# ST_SYS_Board_Clocking.net
KiCad netlist of a schematic drawn in Altium Designer
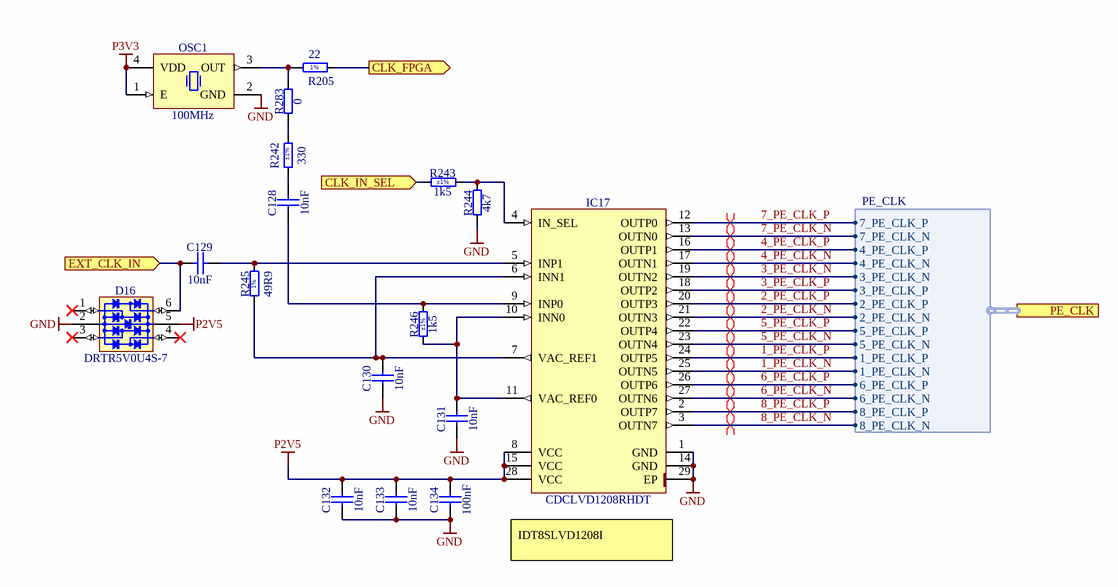
[diagram p0: ST_SYS_Board_Clocking.schdoc]

(export (version "E")
  (design (tool "Eeschema 10.0.6"))
  (components
    (comp (ref "C128")
      (value "10nF")
      (footprint "CAPC0603X33N")
      (description "Non-polarised capacitor")
      (fields
        (field (name "PART NUMBER") "CC0201_10NF_10V_10%_X5R")
        (field (name "VOLTAGE") "10V")
        (field (name "AUTHOR") "CERN DEM JLC")
      )
      (libsource (lib "Capacitors") (part "Capacitor - non polarized"))
    )
    (comp (ref "C129")
      (value "10nF")
      (footprint "CAPC0603X33N")
      (description "Non-polarised capacitor")
      (fields
        (field (name "PART NUMBER") "CC0201_10NF_10V_10%_X5R")
        (field (name "VOLTAGE") "10V")
        (field (name "AUTHOR") "CERN DEM JLC")
      )
      (libsource (lib "Capacitors") (part "Capacitor - non polarized"))
    )
    (comp (ref "C130")
      (value "10nF")
      (footprint "CAPC0603X33N")
      (description "Non-polarised capacitor")
      (fields
        (field (name "PART NUMBER") "CC0201_10NF_10V_10%_X5R")
        (field (name "VOLTAGE") "10V")
        (field (name "AUTHOR") "CERN DEM JLC")
      )
      (libsource (lib "Capacitors") (part "Capacitor - non polarized"))
    )
    (comp (ref "C131")
      (value "10nF")
      (footprint "CAPC0603X33N")
      (description "Non-polarised capacitor")
      (fields
        (field (name "PART NUMBER") "CC0201_10NF_10V_10%_X5R")
        (field (name "VOLTAGE") "10V")
        (field (name "AUTHOR") "CERN DEM JLC")
      )
      (libsource (lib "Capacitors") (part "Capacitor - non polarized"))
    )
    (comp (ref "C132")
      (value "10nF")
      (footprint "CAPC0603X33N")
      (description "Non-polarised capacitor")
      (fields
        (field (name "PART NUMBER") "CC0201_10NF_10V_10%_X5R")
        (field (name "VOLTAGE") "10V")
        (field (name "AUTHOR") "CERN DEM JLC")
      )
      (libsource (lib "Capacitors") (part "Capacitor - non polarized"))
    )
    (comp (ref "C133")
      (value "10nF")
      (footprint "CAPC0603X33N")
      (description "Non-polarised capacitor")
      (fields
        (field (name "PART NUMBER") "CC0201_10NF_10V_10%_X5R")
        (field (name "VOLTAGE") "10V")
        (field (name "AUTHOR") "CERN DEM JLC")
      )
      (libsource (lib "Capacitors") (part "Capacitor - non polarized"))
    )
    (comp (ref "C134")
      (value "100nF")
      (footprint "CAPC1005X55N")
      (description "Non-polarised capacitor")
      (fields
        (field (name "PART NUMBER") "CC0402_100NF_16V_10%_X5R")
        (field (name "VOLTAGE") "16V")
        (field (name "AUTHOR") "CERN DEM JLC")
      )
      (libsource (lib "Capacitors") (part "Capacitor - non polarized"))
    )
    (comp (ref "D16")
      (value "DRTR5V0U4S-7")
      (footprint "SOT65P210X110-6N")
      (description "Integrated Quad Ultra-Low Capacitance ESD Protection")
      (fields (field (name "MANUFACTURER") "DIODES") (field (name "AUTHOR") "GK"))
      (libsource (lib "Diodes") (part "D_TVS_DRTR5V0U4S-7"))
    )
    (comp (ref "IC17")
      (value "CDCLVD1208RHDT")
      (footprint "QFN50P500X500X100-29N-S325")
      (description "2:8 Low Additive Jitter LVDS Buffer")
      (fields
        (field (name "MANUFACTURER") "TEXAS INSTRUMENTS")
        (field (name "MANUFACTURER PART NUMBER") "CDCLVD1208RHD")
        (field (name "AUTHOR") "CERN DEM JLC")
      )
      (libsource (lib "ICs And Semiconductors") (part "CDCLVD1208"))
    )
    (comp (ref "OSC1")
      (value "100MHz")
      (footprint "OSC_ECS_ECS-3953M")
      (description "Oscillator 4 pins 1=E/D 2=GND 3=OUT 4=VDD")
      (fields
        (field (name "PART NUMBER") "OSC_100MHZ_ECS_ECS-3953M-1000-BN")
        (field (name "MANUFACTURER") "ECS")
        (field (name "AUTHOR") "CERN DEM BC")
      )
      (libsource (lib "ICs And Semiconductors") (part "Oscillator 1E 2GND 3OUT 4VDD"))
    )
    (comp (ref "R205")
      (value "22")
      (footprint "RESC1005X40N")
      (description "Resistor - 1%")
      (fields
        (field (name "PART NUMBER") "R0402_22R_1%_0.0625W_100PPM")
        (field (name "POWER") "0.0625W")
        (field (name "AUTHOR") "CERN DEM JLC")
      )
      (libsource (lib "Resistors") (part "Resistor - 1%"))
    )
    (comp (ref "R242")
      (value "330")
      (footprint "RESC1005X40N")
      (description "Resistor - 1%")
      (fields
        (field (name "PART NUMBER") "R0402_330R_1%_0.0625W_100PPM")
        (field (name "POWER") "0.0625W")
        (field (name "TOLERANCE") "±1%")
        (field (name "AUTHOR") "CERN DEM JLC")
      )
      (libsource (lib "Resistors") (part "Resistor - 1%"))
    )
    (comp (ref "R243")
      (value "1k5")
      (footprint "RESC1005X40N")
      (description "Resistor - 1%")
      (fields
        (field (name "TOLERANCE") "±1%")
        (field (name "PART NUMBER") "R0402_1K5_1%_0.0625W_100PPM")
        (field (name "POWER") "0.0625W")
        (field (name "AUTHOR") "CERN DEM JLC")
      )
      (libsource (lib "Resistors") (part "Resistor - 1%"))
    )
    (comp (ref "R244")
      (value "4k7")
      (footprint "RESC1005X40N")
      (description "Resistor - 1%")
      (fields
        (field (name "PART NUMBER") "R0402_4K7_1%_0.0625W_100PPM")
        (field (name "POWER") "0.0625W")
        (field (name "AUTHOR") "CERN DEM JLC")
      )
      (libsource (lib "Resistors") (part "Resistor - 1%"))
    )
    (comp (ref "R245")
      (value "49R9")
      (footprint "RESC1005X40N")
      (description "Resistor - 1%")
      (fields
        (field (name "PART NUMBER") "R0402_49R9_1%_0.0625W_100PPM")
        (field (name "POWER") "0.0625W")
        (field (name "AUTHOR") "CERN DEM JLC")
      )
      (libsource (lib "Resistors") (part "Resistor - 1%"))
    )
    (comp (ref "R246")
      (value "1k5")
      (footprint "RESC1005X40N")
      (description "Resistor - 1%")
      (fields
        (field (name "TOLERANCE") "±1%")
        (field (name "PART NUMBER") "R0402_1K5_1%_0.0625W_100PPM")
        (field (name "POWER") "0.0625W")
        (field (name "AUTHOR") "CERN DEM JLC")
      )
      (libsource (lib "Resistors") (part "Resistor - 1%"))
    )
    (comp (ref "R283")
      (value "0")
      (footprint "RESC1005X40N")
      (description "Resistor")
      (fields
        (field (name "PART NUMBER") "R0402_0R_JUMPER")
        (field (name "MANUFACTURER") "GENERIC")
        (field (name "AUTHOR") "CERN DEM JLC")
      )
      (libsource (lib "Resistors") (part "Resistor"))
    )
  )
  (nets
    (net (code "2") (name "/1_PE_CLK_N") (class "Default")
      (node (ref "IC17") (pin "25") (pinfunction "OUTN5_25") (pintype "output"))
    )
    (net (code "3") (name "/1_PE_CLK_P") (class "Default")
      (node (ref "IC17") (pin "24") (pinfunction "OUTP5_24") (pintype "output"))
    )
    (net (code "4") (name "/2_PE_CLK_N") (class "Default")
      (node (ref "IC17") (pin "21") (pinfunction "OUTN3_21") (pintype "output"))
    )
    (net (code "5") (name "/2_PE_CLK_P") (class "Default")
      (node (ref "IC17") (pin "20") (pinfunction "OUTP3_20") (pintype "output"))
    )
    (net (code "6") (name "/3_PE_CLK_N") (class "Default")
      (node (ref "IC17") (pin "19") (pinfunction "OUTN2_19") (pintype "output"))
    )
    (net (code "7") (name "/3_PE_CLK_P") (class "Default")
      (node (ref "IC17") (pin "18") (pinfunction "OUTP2_18") (pintype "output"))
    )
    (net (code "8") (name "/4_PE_CLK_N") (class "Default")
      (node (ref "IC17") (pin "17") (pinfunction "OUTN1_17") (pintype "output"))
    )
    (net (code "9") (name "/4_PE_CLK_P") (class "Default")
      (node (ref "IC17") (pin "16") (pinfunction "OUTP1_16") (pintype "output"))
    )
    (net (code "10") (name "/5_PE_CLK_N") (class "Default")
      (node (ref "IC17") (pin "23") (pinfunction "OUTN4_23") (pintype "output"))
    )
    (net (code "11") (name "/5_PE_CLK_P") (class "Default")
      (node (ref "IC17") (pin "22") (pinfunction "OUTP4_22") (pintype "output"))
    )
    (net (code "12") (name "/6_PE_CLK_N") (class "Default")
      (node (ref "IC17") (pin "27") (pinfunction "OUTN6_27") (pintype "output"))
    )
    (net (code "13") (name "/6_PE_CLK_P") (class "Default")
      (node (ref "IC17") (pin "26") (pinfunction "OUTP6_26") (pintype "output"))
    )
    (net (code "14") (name "/7_PE_CLK_N") (class "Default")
      (node (ref "IC17") (pin "13") (pinfunction "OUTN0_13") (pintype "output"))
    )
    (net (code "15") (name "/7_PE_CLK_P") (class "Default")
      (node (ref "IC17") (pin "12") (pinfunction "OUTP0_12") (pintype "output"))
    )
    (net (code "16") (name "/8_PE_CLK_N") (class "Default")
      (node (ref "IC17") (pin "3") (pinfunction "OUTN7_3") (pintype "output"))
    )
    (net (code "17") (name "/8_PE_CLK_P") (class "Default")
      (node (ref "IC17") (pin "2") (pinfunction "OUTP7_2") (pintype "output"))
    )
    (net (code "18") (name "/CLK_FPGA") (class "Default")
      (node (ref "R205") (pin "2") (pinfunction "2_2") (pintype "passive"))
    )
    (net (code "19") (name "/CLK_IN_SEL") (class "Default")
      (node (ref "R243") (pin "1") (pinfunction "1_1") (pintype "passive"))
    )
    (net (code "20") (name "/EXT_CLK_IN") (class "Default")
      (node (ref "C129") (pin "1") (pinfunction "1_1") (pintype "passive"))
      (node (ref "D16") (pin "6") (pinfunction "I/O4_6") (pintype "bidirectional"))
    )
    (net (code "22") (name "GND") (class "Default")
      (node (ref "C130") (pin "1") (pinfunction "1_1") (pintype "passive"))
      (node (ref "C131") (pin "1") (pinfunction "1_1") (pintype "passive"))
      (node (ref "C132") (pin "1") (pinfunction "1_1") (pintype "passive"))
      (node (ref "C133") (pin "1") (pinfunction "1_1") (pintype "passive"))
      (node (ref "C134") (pin "1") (pinfunction "1_1") (pintype "passive"))
      (node (ref "D16") (pin "2") (pinfunction "GND_2") (pintype "power_in"))
      (node (ref "IC17") (pin "1") (pinfunction "GND_1") (pintype "power_in"))
      (node (ref "IC17") (pin "14") (pinfunction "GND_14") (pintype "power_in"))
      (node (ref "IC17") (pin "29") (pinfunction "EP_29") (pintype "power_in"))
      (node (ref "OSC1") (pin "2") (pinfunction "GND_2") (pintype "power_in"))
      (node (ref "R244") (pin "1") (pinfunction "1_1") (pintype "passive"))
    )
    (net (code "23") (name "Net-(C128-Pad2)") (class "Default")
      (node (ref "C128") (pin "2") (pinfunction "2_2") (pintype "passive"))
      (node (ref "R242") (pin "1") (pinfunction "1_1") (pintype "passive"))
    )
    (net (code "24") (name "Net-(IC17-INN0)") (class "Default")
      (node (ref "C131") (pin "2") (pinfunction "2_2") (pintype "passive"))
      (node (ref "IC17") (pin "10") (pinfunction "INN0_10") (pintype "input"))
      (node (ref "IC17") (pin "11") (pinfunction "VAC_REF0_11") (pintype "output"))
      (node (ref "R246") (pin "1") (pinfunction "1_1") (pintype "passive"))
    )
    (net (code "25") (name "Net-(IC17-INN1)") (class "Default")
      (node (ref "C130") (pin "2") (pinfunction "2_2") (pintype "passive"))
      (node (ref "IC17") (pin "6") (pinfunction "INN1_6") (pintype "input"))
      (node (ref "IC17") (pin "7") (pinfunction "VAC_REF1_7") (pintype "output"))
      (node (ref "R245") (pin "1") (pinfunction "1_1") (pintype "passive"))
    )
    (net (code "26") (name "Net-(IC17-INP0)") (class "Default")
      (node (ref "C128") (pin "1") (pinfunction "1_1") (pintype "passive"))
      (node (ref "IC17") (pin "9") (pinfunction "INP0_9") (pintype "input"))
      (node (ref "R246") (pin "2") (pinfunction "2_2") (pintype "passive"))
    )
    (net (code "27") (name "Net-(IC17-INP1)") (class "Default")
      (node (ref "C129") (pin "2") (pinfunction "2_2") (pintype "passive"))
      (node (ref "IC17") (pin "5") (pinfunction "INP1_5") (pintype "input"))
      (node (ref "R245") (pin "2") (pinfunction "2_2") (pintype "passive"))
    )
    (net (code "28") (name "Net-(IC17-IN_SEL)") (class "Default")
      (node (ref "IC17") (pin "4") (pinfunction "IN_SEL_4") (pintype "input"))
      (node (ref "R243") (pin "2") (pinfunction "2_2") (pintype "passive"))
      (node (ref "R244") (pin "2") (pinfunction "2_2") (pintype "passive"))
    )
    (net (code "29") (name "Net-(OSC1-OUT)") (class "Default")
      (node (ref "OSC1") (pin "3") (pinfunction "OUT_3") (pintype "output"))
      (node (ref "R205") (pin "1") (pinfunction "1_1") (pintype "passive"))
      (node (ref "R283") (pin "2") (pinfunction "2_2") (pintype "passive"))
    )
    (net (code "30") (name "Net-(R242-Pad2)") (class "Default")
      (node (ref "R242") (pin "2") (pinfunction "2_2") (pintype "passive"))
      (node (ref "R283") (pin "1") (pinfunction "1_1") (pintype "passive"))
    )
    (net (code "31") (name "P2V5") (class "Default")
      (node (ref "C132") (pin "2") (pinfunction "2_2") (pintype "passive"))
      (node (ref "C133") (pin "2") (pinfunction "2_2") (pintype "passive"))
      (node (ref "C134") (pin "2") (pinfunction "2_2") (pintype "passive"))
      (node (ref "D16") (pin "5") (pinfunction "VBUS_5") (pintype "power_in"))
      (node (ref "IC17") (pin "15") (pinfunction "VCC_15") (pintype "power_in"))
      (node (ref "IC17") (pin "28") (pinfunction "VCC_28") (pintype "power_in"))
      (node (ref "IC17") (pin "8") (pinfunction "VCC_8") (pintype "power_in"))
    )
    (net (code "32") (name "P3V3") (class "Default")
      (node (ref "OSC1") (pin "1") (pinfunction "E_1") (pintype "input"))
      (node (ref "OSC1") (pin "4") (pinfunction "VDD_4") (pintype "power_in"))
    )
    (net (code "33") (name "unconnected-(D16-I{slash}O1-Pad1)") (class "Default")
      (node (ref "D16") (pin "1") (pinfunction "I/O1_1") (pintype "bidirectional+no_connect"))
    )
    (net (code "34") (name "unconnected-(D16-I{slash}O2-Pad3)") (class "Default")
      (node (ref "D16") (pin "3") (pinfunction "I/O2_3") (pintype "bidirectional+no_connect"))
    )
    (net (code "35") (name "unconnected-(D16-I{slash}O3-Pad4)") (class "Default")
      (node (ref "D16") (pin "4") (pinfunction "I/O3_4") (pintype "bidirectional+no_connect"))
    )
  )
)
